# Controller2.net
KiCad netlist of a schematic drawn in EAGLE
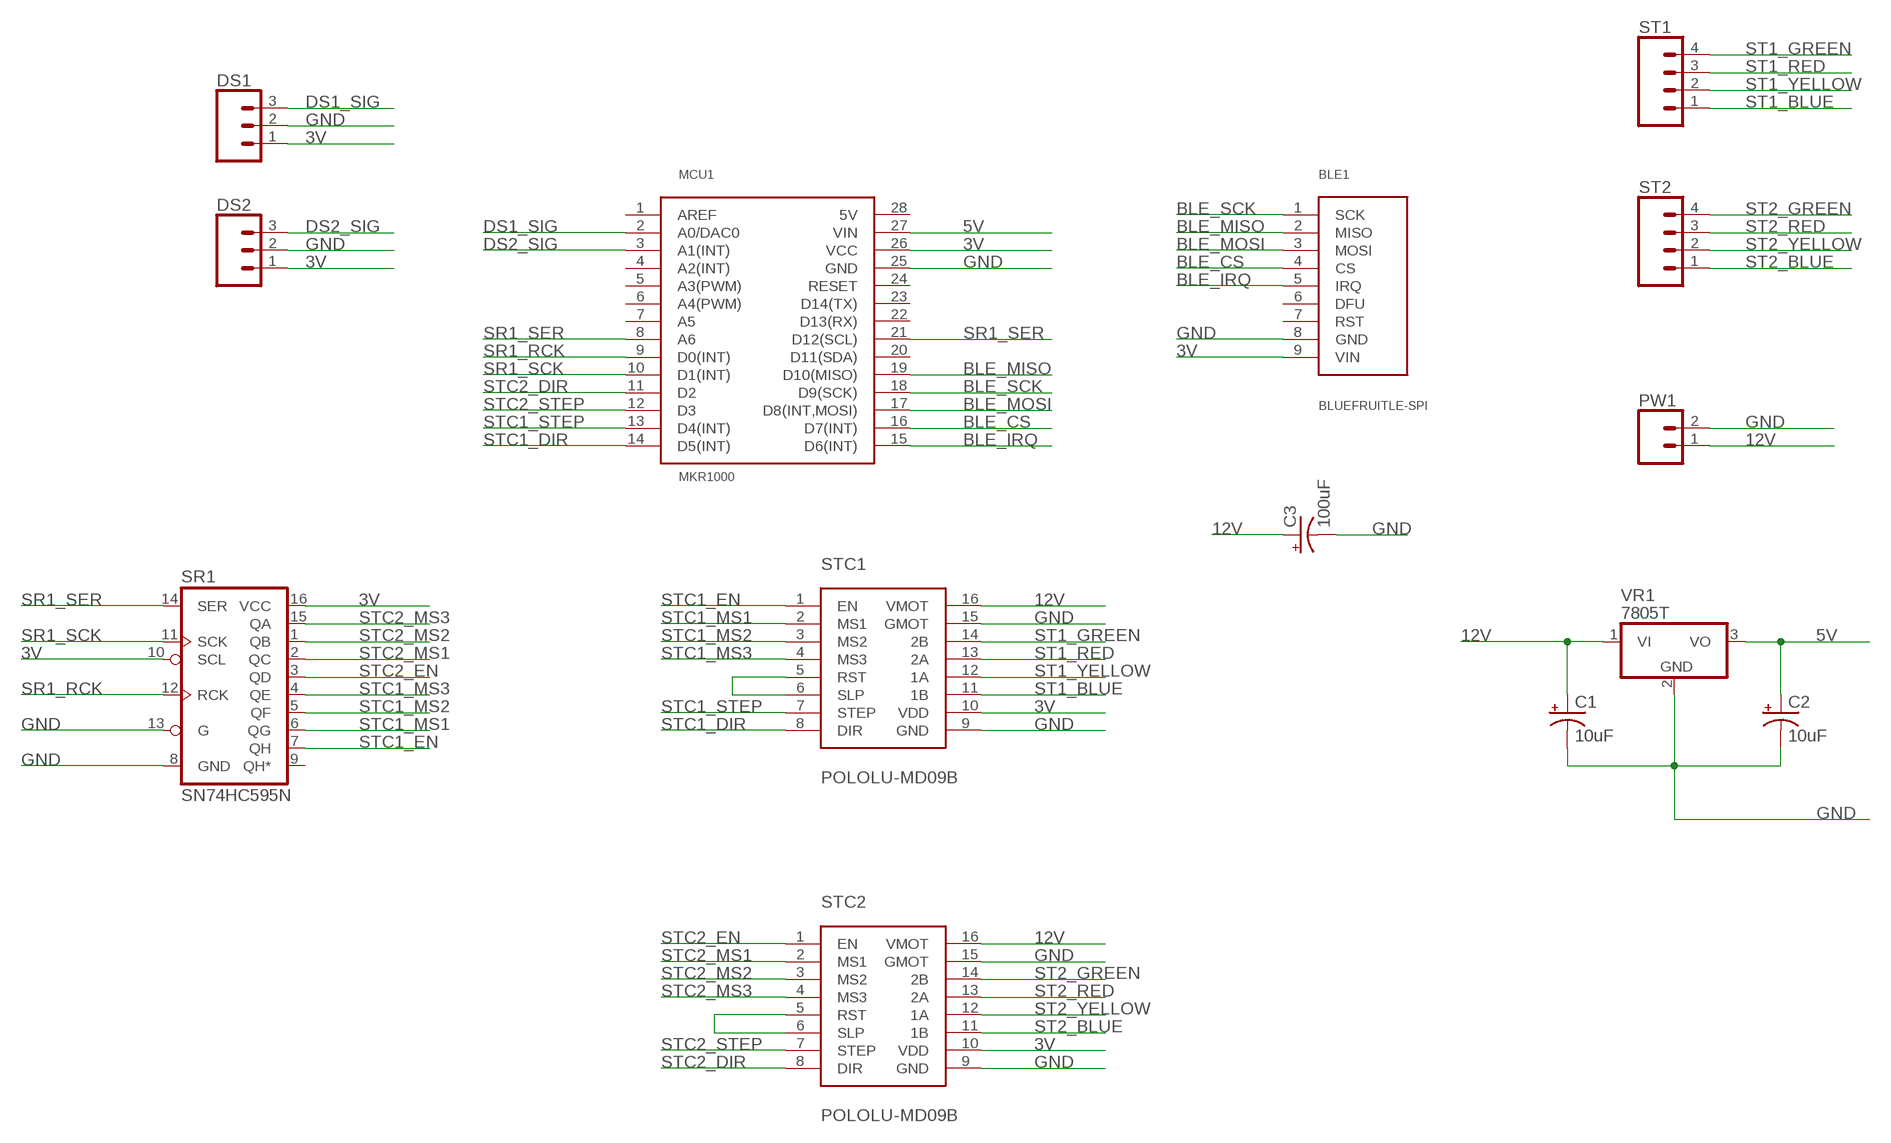
[diagram p0: schematic, sheet 1]

(export (version "E")
  (design (tool "Eeschema 10.0.6"))
  (components
    (comp (ref "BLE1")
      (value "BLUEFRUITLE-SPI")
      (footprint "eagle-import:BLUEFRUITLE-SPI-SOCKET")
      (libsource (lib "eagle-import") (part "BLUEFRUITLE-SPI"))
    )
    (comp (ref "C1")
      (value "10uF")
      (footprint "eagle-import:E2-5")
      (libsource (lib "eagle-import") (part "CPOL-USE2-5"))
    )
    (comp (ref "C2")
      (value "10uF")
      (footprint "eagle-import:E2-5")
      (libsource (lib "eagle-import") (part "CPOL-USE2-5"))
    )
    (comp (ref "C3")
      (value "100uF")
      (footprint "eagle-import:E2-5")
      (libsource (lib "eagle-import") (part "CPOL-USE2-5"))
    )
    (comp (ref "DS1")
      (value "CONN_03LONGPADS")
      (footprint "eagle-import:1X03_LONGPADS")
      (libsource (lib "eagle-import") (part "CONN_03LONGPADS"))
    )
    (comp (ref "DS2")
      (value "CONN_03LONGPADS")
      (footprint "eagle-import:1X03_LONGPADS")
      (libsource (lib "eagle-import") (part "CONN_03LONGPADS"))
    )
    (comp (ref "MCU1")
      (value "MKR1000")
      (footprint "eagle-import:MKR1000-SOCKET")
      (libsource (lib "eagle-import") (part "MKR1000"))
    )
    (comp (ref "PW1")
      (value "CONN_025MM")
      (footprint "eagle-import:SCREWTERMINAL-5MM-2")
      (libsource (lib "eagle-import") (part "CONN_025MM"))
    )
    (comp (ref "SR1")
      (value "SN74HC595N")
      (footprint "eagle-import:DIP16")
      (libsource (lib "eagle-import") (part "74595NHC"))
    )
    (comp (ref "ST1")
      (value "CONN_04LONGPADS")
      (footprint "eagle-import:1X04_LONGPADS")
      (libsource (lib "eagle-import") (part "CONN_04LONGPADS"))
    )
    (comp (ref "ST2")
      (value "CONN_04LONGPADS")
      (footprint "eagle-import:1X04_LONGPADS")
      (libsource (lib "eagle-import") (part "CONN_04LONGPADS"))
    )
    (comp (ref "STC1")
      (value "POLOLU-MD09B")
      (footprint "eagle-import:POLOLU-MD09B")
      (libsource (lib "eagle-import") (part "POLOLU-MD09B"))
    )
    (comp (ref "STC2")
      (value "POLOLU-MD09B")
      (footprint "eagle-import:POLOLU-MD09B")
      (libsource (lib "eagle-import") (part "POLOLU-MD09B"))
    )
    (comp (ref "VR1")
      (value "7805T")
      (footprint "eagle-import:TO220H")
      (libsource (lib "eagle-import") (part "78T05"))
    )
  )
  (nets
    (net (code "1") (name "/3V") (class "Default")
      (node (ref "BLE1") (pin "9") (pinfunction "VIN_9") (pintype "bidirectional"))
      (node (ref "DS1") (pin "1") (pinfunction "1_1") (pintype "passive"))
      (node (ref "DS2") (pin "1") (pinfunction "1_1") (pintype "passive"))
      (node (ref "MCU1") (pin "26") (pinfunction "VCC_26") (pintype "bidirectional"))
      (node (ref "SR1") (pin "10") (pinfunction "SCL_10") (pintype "input"))
      (node (ref "SR1") (pin "16") (pinfunction "VCC_16") (pintype "power_in"))
      (node (ref "STC1") (pin "10") (pinfunction "VDD_10") (pintype "bidirectional"))
      (node (ref "STC2") (pin "10") (pinfunction "VDD_10") (pintype "bidirectional"))
    )
    (net (code "2") (name "/5V") (class "Default")
      (node (ref "C2") (pin "+") (pinfunction "+_+") (pintype "passive"))
      (node (ref "MCU1") (pin "27") (pinfunction "VIN_27") (pintype "bidirectional"))
      (node (ref "VR1") (pin "3") (pinfunction "VO_3") (pintype "passive"))
    )
    (net (code "3") (name "/12V") (class "Default")
      (node (ref "C1") (pin "+") (pinfunction "+_+") (pintype "passive"))
      (node (ref "C3") (pin "+") (pinfunction "+_+") (pintype "passive"))
      (node (ref "PW1") (pin "1") (pinfunction "1_1") (pintype "passive"))
      (node (ref "STC1") (pin "16") (pinfunction "VMOT_16") (pintype "bidirectional"))
      (node (ref "STC2") (pin "16") (pinfunction "VMOT_16") (pintype "bidirectional"))
      (node (ref "VR1") (pin "1") (pinfunction "VI_1") (pintype "input"))
    )
    (net (code "4") (name "/BLE_CS") (class "Default")
      (node (ref "BLE1") (pin "4") (pinfunction "CS_4") (pintype "bidirectional"))
      (node (ref "MCU1") (pin "16") (pinfunction "D7(INT)_16") (pintype "bidirectional"))
    )
    (net (code "5") (name "/BLE_IRQ") (class "Default")
      (node (ref "BLE1") (pin "5") (pinfunction "IRQ_5") (pintype "bidirectional"))
      (node (ref "MCU1") (pin "15") (pinfunction "D6(INT)_15") (pintype "bidirectional"))
    )
    (net (code "6") (name "/BLE_MISO") (class "Default")
      (node (ref "BLE1") (pin "2") (pinfunction "MISO_2") (pintype "bidirectional"))
      (node (ref "MCU1") (pin "19") (pinfunction "D10(MISO)_19") (pintype "bidirectional"))
    )
    (net (code "7") (name "/BLE_MOSI") (class "Default")
      (node (ref "BLE1") (pin "3") (pinfunction "MOSI_3") (pintype "bidirectional"))
      (node (ref "MCU1") (pin "17") (pinfunction "D8(INT,MOSI)_17") (pintype "bidirectional"))
    )
    (net (code "8") (name "/BLE_SCK") (class "Default")
      (node (ref "BLE1") (pin "1") (pinfunction "SCK_1") (pintype "bidirectional"))
      (node (ref "MCU1") (pin "18") (pinfunction "D9(SCK)_18") (pintype "bidirectional"))
    )
    (net (code "9") (name "/DS1_SIG") (class "Default")
      (node (ref "DS1") (pin "3") (pinfunction "3_3") (pintype "passive"))
      (node (ref "MCU1") (pin "2") (pinfunction "A0/DAC0_2") (pintype "bidirectional"))
    )
    (net (code "10") (name "/DS2_SIG") (class "Default")
      (node (ref "DS2") (pin "3") (pinfunction "3_3") (pintype "passive"))
      (node (ref "MCU1") (pin "3") (pinfunction "A1(INT)_3") (pintype "bidirectional"))
    )
    (net (code "11") (name "/GND") (class "Default")
      (node (ref "BLE1") (pin "8") (pinfunction "GND_8") (pintype "bidirectional"))
      (node (ref "C1") (pin "-") (pinfunction "-_-") (pintype "passive"))
      (node (ref "C2") (pin "-") (pinfunction "-_-") (pintype "passive"))
      (node (ref "C3") (pin "-") (pinfunction "-_-") (pintype "passive"))
      (node (ref "DS1") (pin "2") (pinfunction "2_2") (pintype "passive"))
      (node (ref "DS2") (pin "2") (pinfunction "2_2") (pintype "passive"))
      (node (ref "MCU1") (pin "25") (pinfunction "GND_25") (pintype "bidirectional"))
      (node (ref "PW1") (pin "2") (pinfunction "2_2") (pintype "passive"))
      (node (ref "SR1") (pin "13") (pinfunction "G_13") (pintype "input"))
      (node (ref "SR1") (pin "8") (pinfunction "GND_8") (pintype "power_in"))
      (node (ref "STC1") (pin "15") (pinfunction "GMOT_15") (pintype "bidirectional"))
      (node (ref "STC1") (pin "9") (pinfunction "GND_9") (pintype "bidirectional"))
      (node (ref "STC2") (pin "15") (pinfunction "GMOT_15") (pintype "bidirectional"))
      (node (ref "STC2") (pin "9") (pinfunction "GND_9") (pintype "bidirectional"))
      (node (ref "VR1") (pin "2") (pinfunction "GND_2") (pintype "passive"))
    )
    (net (code "12") (name "/SR1_RCK") (class "Default")
      (node (ref "MCU1") (pin "9") (pinfunction "D0(INT)_9") (pintype "bidirectional"))
      (node (ref "SR1") (pin "12") (pinfunction "RCK_12") (pintype "input"))
    )
    (net (code "13") (name "/SR1_SCK") (class "Default")
      (node (ref "MCU1") (pin "10") (pinfunction "D1(INT)_10") (pintype "bidirectional"))
      (node (ref "SR1") (pin "11") (pinfunction "SCK_11") (pintype "input"))
    )
    (net (code "14") (name "/SR1_SER") (class "Default")
      (node (ref "MCU1") (pin "21") (pinfunction "D12(SCL)_21") (pintype "bidirectional"))
      (node (ref "MCU1") (pin "8") (pinfunction "A6_8") (pintype "bidirectional"))
      (node (ref "SR1") (pin "14") (pinfunction "SER_14") (pintype "input"))
    )
    (net (code "15") (name "/ST1_BLUE") (class "Default")
      (node (ref "ST1") (pin "1") (pinfunction "1_1") (pintype "passive"))
      (node (ref "STC1") (pin "11") (pinfunction "1B_11") (pintype "bidirectional"))
    )
    (net (code "16") (name "/ST1_GREEN") (class "Default")
      (node (ref "ST1") (pin "4") (pinfunction "4_4") (pintype "passive"))
      (node (ref "STC1") (pin "14") (pinfunction "2B_14") (pintype "bidirectional"))
    )
    (net (code "17") (name "/ST1_RED") (class "Default")
      (node (ref "ST1") (pin "3") (pinfunction "3_3") (pintype "passive"))
      (node (ref "STC1") (pin "13") (pinfunction "2A_13") (pintype "bidirectional"))
    )
    (net (code "18") (name "/ST1_YELLOW") (class "Default")
      (node (ref "ST1") (pin "2") (pinfunction "2_2") (pintype "passive"))
      (node (ref "STC1") (pin "12") (pinfunction "1A_12") (pintype "bidirectional"))
    )
    (net (code "19") (name "/ST2_BLUE") (class "Default")
      (node (ref "ST2") (pin "1") (pinfunction "1_1") (pintype "passive"))
      (node (ref "STC2") (pin "11") (pinfunction "1B_11") (pintype "bidirectional"))
    )
    (net (code "20") (name "/ST2_GREEN") (class "Default")
      (node (ref "ST2") (pin "4") (pinfunction "4_4") (pintype "passive"))
      (node (ref "STC2") (pin "14") (pinfunction "2B_14") (pintype "bidirectional"))
    )
    (net (code "21") (name "/ST2_RED") (class "Default")
      (node (ref "ST2") (pin "3") (pinfunction "3_3") (pintype "passive"))
      (node (ref "STC2") (pin "13") (pinfunction "2A_13") (pintype "bidirectional"))
    )
    (net (code "22") (name "/ST2_YELLOW") (class "Default")
      (node (ref "ST2") (pin "2") (pinfunction "2_2") (pintype "passive"))
      (node (ref "STC2") (pin "12") (pinfunction "1A_12") (pintype "bidirectional"))
    )
    (net (code "23") (name "/STC1_DIR") (class "Default")
      (node (ref "MCU1") (pin "14") (pinfunction "D5(INT)_14") (pintype "bidirectional"))
      (node (ref "STC1") (pin "8") (pinfunction "DIR_8") (pintype "bidirectional"))
    )
    (net (code "24") (name "/STC1_EN") (class "Default")
      (node (ref "SR1") (pin "7") (pinfunction "QH_7") (pintype "tri_state"))
      (node (ref "STC1") (pin "1") (pinfunction "EN_1") (pintype "bidirectional"))
    )
    (net (code "25") (name "/STC1_MS1") (class "Default")
      (node (ref "SR1") (pin "6") (pinfunction "QG_6") (pintype "tri_state"))
      (node (ref "STC1") (pin "2") (pinfunction "MS1_2") (pintype "bidirectional"))
    )
    (net (code "26") (name "/STC1_MS2") (class "Default")
      (node (ref "SR1") (pin "5") (pinfunction "QF_5") (pintype "tri_state"))
      (node (ref "STC1") (pin "3") (pinfunction "MS2_3") (pintype "bidirectional"))
    )
    (net (code "27") (name "/STC1_MS3") (class "Default")
      (node (ref "SR1") (pin "4") (pinfunction "QE_4") (pintype "tri_state"))
      (node (ref "STC1") (pin "4") (pinfunction "MS3_4") (pintype "bidirectional"))
    )
    (net (code "28") (name "/STC1_STEP") (class "Default")
      (node (ref "MCU1") (pin "13") (pinfunction "D4(INT)_13") (pintype "bidirectional"))
      (node (ref "STC1") (pin "7") (pinfunction "STEP_7") (pintype "bidirectional"))
    )
    (net (code "29") (name "/STC2_DIR") (class "Default")
      (node (ref "MCU1") (pin "11") (pinfunction "D2_11") (pintype "bidirectional"))
      (node (ref "STC2") (pin "8") (pinfunction "DIR_8") (pintype "bidirectional"))
    )
    (net (code "30") (name "/STC2_EN") (class "Default")
      (node (ref "SR1") (pin "3") (pinfunction "QD_3") (pintype "tri_state"))
      (node (ref "STC2") (pin "1") (pinfunction "EN_1") (pintype "bidirectional"))
    )
    (net (code "31") (name "/STC2_MS1") (class "Default")
      (node (ref "SR1") (pin "2") (pinfunction "QC_2") (pintype "tri_state"))
      (node (ref "STC2") (pin "2") (pinfunction "MS1_2") (pintype "bidirectional"))
    )
    (net (code "32") (name "/STC2_MS2") (class "Default")
      (node (ref "SR1") (pin "1") (pinfunction "QB_1") (pintype "tri_state"))
      (node (ref "STC2") (pin "3") (pinfunction "MS2_3") (pintype "bidirectional"))
    )
    (net (code "33") (name "/STC2_MS3") (class "Default")
      (node (ref "SR1") (pin "15") (pinfunction "QA_15") (pintype "tri_state"))
      (node (ref "STC2") (pin "4") (pinfunction "MS3_4") (pintype "bidirectional"))
    )
    (net (code "34") (name "/STC2_STEP") (class "Default")
      (node (ref "MCU1") (pin "12") (pinfunction "D3_12") (pintype "bidirectional"))
      (node (ref "STC2") (pin "7") (pinfunction "STEP_7") (pintype "bidirectional"))
    )
    (net (code "35") (name "Net-(STC1-RST)") (class "Default")
      (node (ref "STC1") (pin "5") (pinfunction "RST_5") (pintype "bidirectional"))
      (node (ref "STC1") (pin "6") (pinfunction "SLP_6") (pintype "bidirectional"))
    )
    (net (code "36") (name "Net-(STC2-RST)") (class "Default")
      (node (ref "STC2") (pin "5") (pinfunction "RST_5") (pintype "bidirectional"))
      (node (ref "STC2") (pin "6") (pinfunction "SLP_6") (pintype "bidirectional"))
    )
    (net (code "37") (name "unconnected-(BLE1-DFU-Pad6)") (class "Default")
      (node (ref "BLE1") (pin "6") (pinfunction "DFU_6") (pintype "bidirectional"))
    )
    (net (code "38") (name "unconnected-(BLE1-RST-Pad7)") (class "Default")
      (node (ref "BLE1") (pin "7") (pinfunction "RST_7") (pintype "bidirectional"))
    )
    (net (code "39") (name "unconnected-(MCU1-5V-Pad28)") (class "Default")
      (node (ref "MCU1") (pin "28") (pinfunction "5V_28") (pintype "bidirectional"))
    )
    (net (code "40") (name "unconnected-(MCU1-A2(INT)-Pad4)") (class "Default")
      (node (ref "MCU1") (pin "4") (pinfunction "A2(INT)_4") (pintype "bidirectional"))
    )
    (net (code "41") (name "unconnected-(MCU1-A3(PWM)-Pad5)") (class "Default")
      (node (ref "MCU1") (pin "5") (pinfunction "A3(PWM)_5") (pintype "bidirectional"))
    )
    (net (code "42") (name "unconnected-(MCU1-A4(PWM)-Pad6)") (class "Default")
      (node (ref "MCU1") (pin "6") (pinfunction "A4(PWM)_6") (pintype "bidirectional"))
    )
    (net (code "43") (name "unconnected-(MCU1-A5-Pad7)") (class "Default")
      (node (ref "MCU1") (pin "7") (pinfunction "A5_7") (pintype "bidirectional"))
    )
    (net (code "44") (name "unconnected-(MCU1-AREF-Pad1)") (class "Default")
      (node (ref "MCU1") (pin "1") (pinfunction "AREF_1") (pintype "bidirectional"))
    )
    (net (code "45") (name "unconnected-(MCU1-D11(SDA)-Pad20)") (class "Default")
      (node (ref "MCU1") (pin "20") (pinfunction "D11(SDA)_20") (pintype "bidirectional"))
    )
    (net (code "46") (name "unconnected-(MCU1-D13(RX)-Pad22)") (class "Default")
      (node (ref "MCU1") (pin "22") (pinfunction "D13(RX)_22") (pintype "bidirectional"))
    )
    (net (code "47") (name "unconnected-(MCU1-D14(TX)-Pad23)") (class "Default")
      (node (ref "MCU1") (pin "23") (pinfunction "D14(TX)_23") (pintype "bidirectional"))
    )
    (net (code "48") (name "unconnected-(MCU1-RESET-Pad24)") (class "Default")
      (node (ref "MCU1") (pin "24") (pinfunction "RESET_24") (pintype "bidirectional"))
    )
    (net (code "49") (name "unconnected-(SR1-QH*-Pad9)") (class "Default")
      (node (ref "SR1") (pin "9") (pinfunction "QH*_9") (pintype "tri_state"))
    )
  )
)
